# switchless_icsp_borti.net
KiCad netlist of a schematic drawn in EAGLE
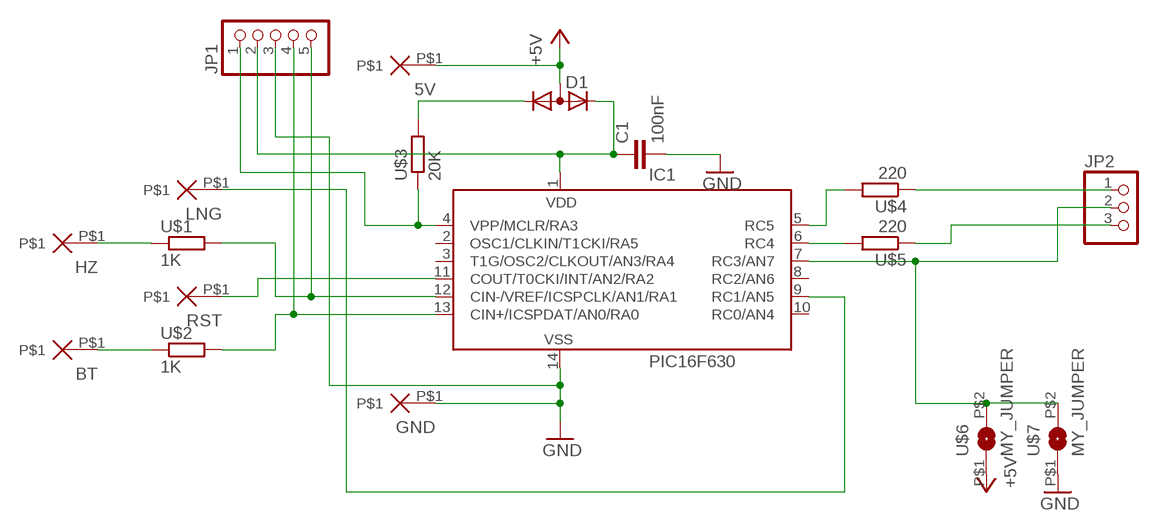
[diagram p0: schematic, sheet 1]

(export (version "E")
  (design (tool "Eeschema 10.0.6"))
  (components
    (comp (ref "5V")
      (value "PAD")
      (footprint "eagle-import:PADS")
      (libsource (lib "eagle-import") (part "PAD"))
    )
    (comp (ref "BT")
      (value "PAD")
      (footprint "eagle-import:PADS")
      (libsource (lib "eagle-import") (part "PAD"))
    )
    (comp (ref "C1")
      (value "100nF")
      (footprint "eagle-import:Z0805")
      (libsource (lib "eagle-import") (part "C0805"))
    )
    (comp (ref "D1")
      (value "DIODE_CA-AC__")
      (footprint "eagle-import:SOT23C")
      (libsource (lib "eagle-import") (part "DIODE_CA-AC__"))
    )
    (comp (ref "GND")
      (value "PAD")
      (footprint "eagle-import:PADS")
      (libsource (lib "eagle-import") (part "PAD"))
    )
    (comp (ref "HZ")
      (value "PAD")
      (footprint "eagle-import:PADS")
      (libsource (lib "eagle-import") (part "PAD"))
    )
    (comp (ref "IC1")
      (value "PIC16F630")
      (footprint "eagle-import:PIC16F630")
      (libsource (lib "eagle-import") (part "PIC16F630"))
    )
    (comp (ref "JP1")
      (value "PINHD-1X5")
      (footprint "eagle-import:1X05")
      (libsource (lib "eagle-import") (part "PINHD-1X5"))
    )
    (comp (ref "JP2")
      (value "PINHD-1X3")
      (footprint "eagle-import:1X03")
      (libsource (lib "eagle-import") (part "PINHD-1X3"))
    )
    (comp (ref "LNG")
      (value "PAD")
      (footprint "eagle-import:PADS")
      (libsource (lib "eagle-import") (part "PAD"))
    )
    (comp (ref "RST")
      (value "PAD")
      (footprint "eagle-import:PADS")
      (libsource (lib "eagle-import") (part "PAD"))
    )
    (comp (ref "U$1")
      (value "1K")
      (footprint "eagle-import:Z0805")
      (libsource (lib "eagle-import") (part "R0805"))
    )
    (comp (ref "U$2")
      (value "1K")
      (footprint "eagle-import:Z0805")
      (libsource (lib "eagle-import") (part "R0805"))
    )
    (comp (ref "U$3")
      (value "20K")
      (footprint "eagle-import:Z0805")
      (libsource (lib "eagle-import") (part "R0805"))
    )
    (comp (ref "U$4")
      (value "220")
      (footprint "eagle-import:Z0805")
      (libsource (lib "eagle-import") (part "R0805"))
    )
    (comp (ref "U$5")
      (value "220")
      (footprint "eagle-import:Z0805")
      (libsource (lib "eagle-import") (part "R0805"))
    )
    (comp (ref "U$6")
      (value "MY_JUMPER")
      (footprint "eagle-import:MYJUMP")
      (libsource (lib "eagle-import") (part "MY_JUMPER"))
    )
    (comp (ref "U$7")
      (value "MY_JUMPER")
      (footprint "eagle-import:MYJUMP")
      (libsource (lib "eagle-import") (part "MY_JUMPER"))
    )
  )
  (nets
    (net (code "1") (name "+5V") (class "Default")
      (node (ref "5V") (pin "P$1") (pinfunction "P$1_P$1") (pintype "bidirectional"))
      (node (ref "D1") (pin "3") (pinfunction "A_3") (pintype "passive"))
      (node (ref "U$6") (pin "P$1") (pinfunction "1_P$1") (pintype "passive"))
    )
    (net (code "2") (name "GND") (class "Default")
      (node (ref "C1") (pin "2") (pinfunction "2_2") (pintype "passive"))
      (node (ref "GND") (pin "P$1") (pinfunction "P$1_P$1") (pintype "bidirectional"))
      (node (ref "IC1") (pin "14") (pinfunction "VSS_14") (pintype "power_in"))
      (node (ref "JP1") (pin "3") (pinfunction "3_3") (pintype "passive"))
      (node (ref "U$7") (pin "P$1") (pinfunction "1_P$1") (pintype "passive"))
    )
    (net (code "3") (name "Net-(BT-PadP$1)") (class "Default")
      (node (ref "BT") (pin "P$1") (pinfunction "P$1_P$1") (pintype "bidirectional"))
      (node (ref "U$2") (pin "1") (pinfunction "1_1") (pintype "passive"))
    )
    (net (code "4") (name "Net-(D1-K1)") (class "Default")
      (node (ref "D1") (pin "1") (pinfunction "K1_1") (pintype "passive"))
      (node (ref "U$3") (pin "2") (pinfunction "2_2") (pintype "passive"))
    )
    (net (code "5") (name "Net-(D1-K2)") (class "Default")
      (node (ref "C1") (pin "1") (pinfunction "1_1") (pintype "passive"))
      (node (ref "D1") (pin "2") (pinfunction "K2_2") (pintype "passive"))
      (node (ref "IC1") (pin "1") (pinfunction "VDD_1") (pintype "power_in"))
      (node (ref "JP1") (pin "2") (pinfunction "2_2") (pintype "passive"))
    )
    (net (code "6") (name "Net-(HZ-PadP$1)") (class "Default")
      (node (ref "HZ") (pin "P$1") (pinfunction "P$1_P$1") (pintype "bidirectional"))
      (node (ref "U$1") (pin "1") (pinfunction "1_1") (pintype "passive"))
    )
    (net (code "7") (name "Net-(IC1-CIN+{slash}ICSPDAT{slash}AN0{slash}RA0)") (class "Default")
      (node (ref "IC1") (pin "13") (pinfunction "CIN+/ICSPDAT/AN0/RA0_13") (pintype "bidirectional"))
      (node (ref "JP1") (pin "4") (pinfunction "4_4") (pintype "passive"))
      (node (ref "U$2") (pin "2") (pinfunction "2_2") (pintype "passive"))
    )
    (net (code "8") (name "Net-(IC1-CIN-{slash}VREF{slash}ICSPCLK{slash}AN1{slash}RA1)") (class "Default")
      (node (ref "IC1") (pin "12") (pinfunction "CIN-/VREF/ICSPCLK/AN1/RA1_12") (pintype "bidirectional"))
      (node (ref "JP1") (pin "5") (pinfunction "5_5") (pintype "passive"))
      (node (ref "U$1") (pin "2") (pinfunction "2_2") (pintype "passive"))
    )
    (net (code "9") (name "Net-(IC1-COUT{slash}T0CKI{slash}INT{slash}AN2{slash}RA2)") (class "Default")
      (node (ref "IC1") (pin "11") (pinfunction "COUT/T0CKI/INT/AN2/RA2_11") (pintype "bidirectional"))
      (node (ref "RST") (pin "P$1") (pinfunction "P$1_P$1") (pintype "bidirectional"))
    )
    (net (code "10") (name "Net-(IC1-RC1{slash}AN5)") (class "Default")
      (node (ref "IC1") (pin "9") (pinfunction "RC1/AN5_9") (pintype "bidirectional"))
      (node (ref "LNG") (pin "P$1") (pinfunction "P$1_P$1") (pintype "bidirectional"))
    )
    (net (code "11") (name "Net-(IC1-RC3{slash}AN7)") (class "Default")
      (node (ref "IC1") (pin "7") (pinfunction "RC3/AN7_7") (pintype "bidirectional"))
      (node (ref "JP2") (pin "2") (pinfunction "2_2") (pintype "passive"))
      (node (ref "U$6") (pin "P$2") (pinfunction "2_P$2") (pintype "passive"))
      (node (ref "U$7") (pin "P$2") (pinfunction "2_P$2") (pintype "passive"))
    )
    (net (code "12") (name "Net-(IC1-RC4)") (class "Default")
      (node (ref "IC1") (pin "6") (pinfunction "RC4_6") (pintype "bidirectional"))
      (node (ref "U$5") (pin "2") (pinfunction "2_2") (pintype "passive"))
    )
    (net (code "13") (name "Net-(IC1-RC5)") (class "Default")
      (node (ref "IC1") (pin "5") (pinfunction "RC5_5") (pintype "bidirectional"))
      (node (ref "U$4") (pin "2") (pinfunction "2_2") (pintype "passive"))
    )
    (net (code "14") (name "Net-(IC1-VPP{slash}MCLR{slash}RA3)") (class "Default")
      (node (ref "IC1") (pin "4") (pinfunction "VPP/MCLR/RA3_4") (pintype "input"))
      (node (ref "JP1") (pin "1") (pinfunction "1_1") (pintype "passive"))
      (node (ref "U$3") (pin "1") (pinfunction "1_1") (pintype "passive"))
    )
    (net (code "15") (name "Net-(JP2-Pad1)") (class "Default")
      (node (ref "JP2") (pin "1") (pinfunction "1_1") (pintype "passive"))
      (node (ref "U$4") (pin "1") (pinfunction "1_1") (pintype "passive"))
    )
    (net (code "16") (name "Net-(JP2-Pad3)") (class "Default")
      (node (ref "JP2") (pin "3") (pinfunction "3_3") (pintype "passive"))
      (node (ref "U$5") (pin "1") (pinfunction "1_1") (pintype "passive"))
    )
    (net (code "17") (name "unconnected-(IC1-OSC1{slash}CLKIN{slash}T1CKI{slash}RA5-Pad2)") (class "Default")
      (node (ref "IC1") (pin "2") (pinfunction "OSC1/CLKIN/T1CKI/RA5_2") (pintype "bidirectional"))
    )
    (net (code "18") (name "unconnected-(IC1-RC0{slash}AN4-Pad10)") (class "Default")
      (node (ref "IC1") (pin "10") (pinfunction "RC0/AN4_10") (pintype "bidirectional"))
    )
    (net (code "19") (name "unconnected-(IC1-RC2{slash}AN6-Pad8)") (class "Default")
      (node (ref "IC1") (pin "8") (pinfunction "RC2/AN6_8") (pintype "bidirectional"))
    )
    (net (code "20") (name "unconnected-(IC1-T1G{slash}OSC2{slash}CLKOUT{slash}AN3{slash}RA4-Pad3)") (class "Default")
      (node (ref "IC1") (pin "3") (pinfunction "T1G/OSC2/CLKOUT/AN3/RA4_3") (pintype "bidirectional"))
    )
  )
)
